# Power_Board_v2.net
KiCad netlist of a schematic drawn in EAGLE
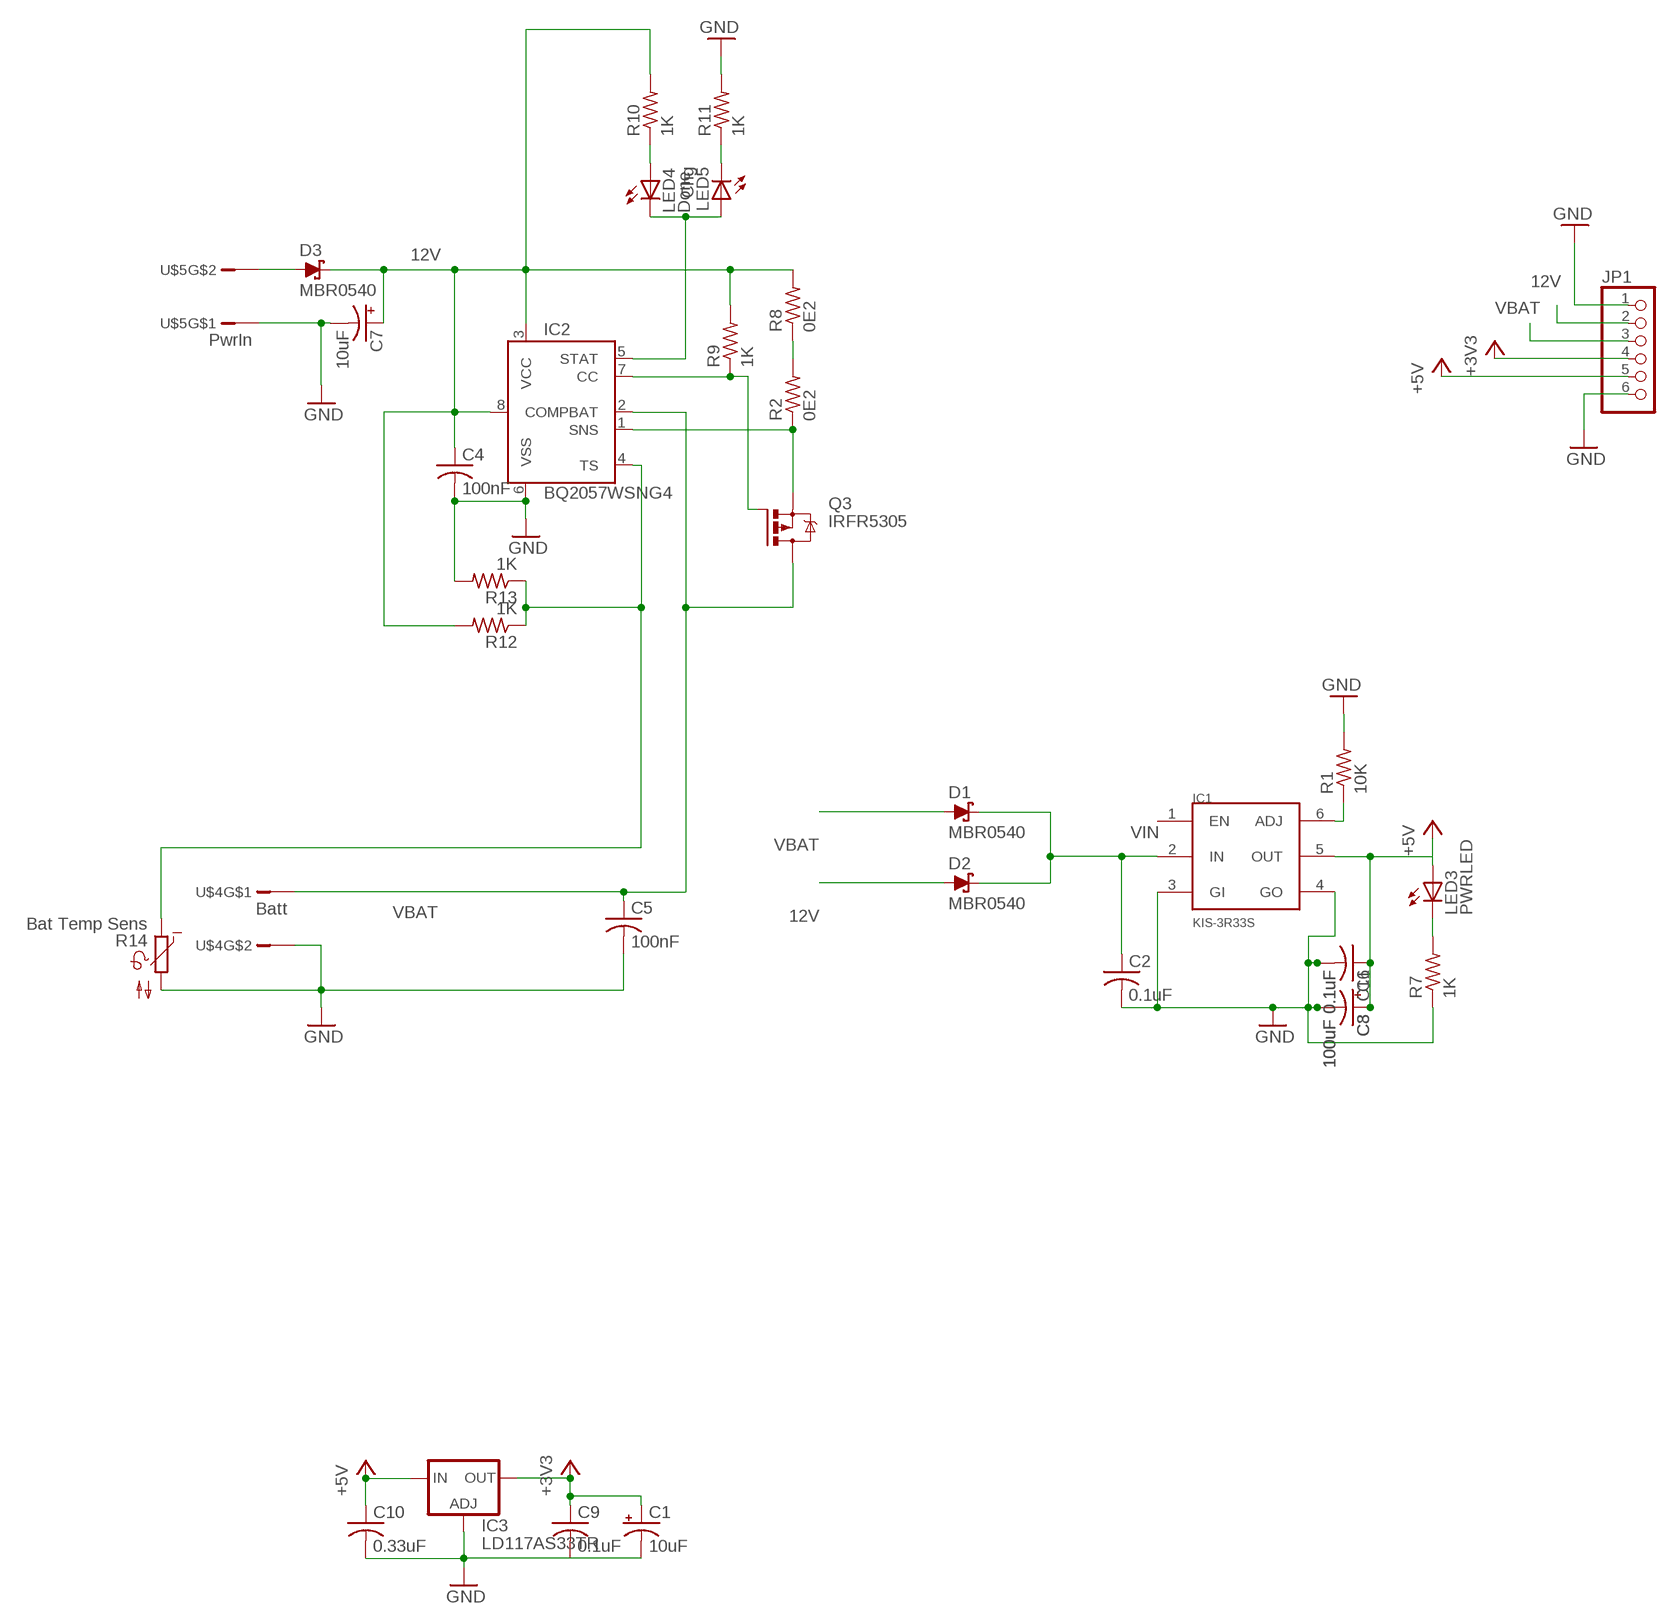
[diagram p0: schematic, sheet 1]

(export (version "E")
  (design (tool "Eeschema 10.0.6"))
  (components
    (comp (ref "C1")
      (value "10uF")
      (footprint "eagle-import:153CLV-0405")
      (libsource (lib "eagle-import") (part "CPOL-US153CLV-0405"))
    )
    (comp (ref "C2")
      (value "0.1uF")
      (footprint "eagle-import:C0805K")
      (libsource (lib "eagle-import") (part "C-USC0805K"))
    )
    (comp (ref "C3")
      (value "100uF")
      (footprint "eagle-import:PANASONIC_D")
      (libsource (lib "eagle-import") (part "CPOL-USD"))
    )
    (comp (ref "C4")
      (value "100nF")
      (footprint "eagle-import:C0805K")
      (libsource (lib "eagle-import") (part "C-USC0805K"))
    )
    (comp (ref "C5")
      (value "100nF")
      (footprint "eagle-import:C0805K")
      (libsource (lib "eagle-import") (part "C-USC0805K"))
    )
    (comp (ref "C6")
      (value "0.1uF")
      (footprint "eagle-import:C0805K")
      (libsource (lib "eagle-import") (part "C-USC0805K"))
    )
    (comp (ref "C7")
      (value "10uF")
      (footprint "eagle-import:153CLV-0405")
      (libsource (lib "eagle-import") (part "CPOL-US153CLV-0405"))
    )
    (comp (ref "C8")
      (value "100uF")
      (footprint "eagle-import:PANASONIC_D")
      (libsource (lib "eagle-import") (part "CPOL-USD"))
    )
    (comp (ref "C9")
      (value "0.1uF")
      (footprint "eagle-import:C0805K")
      (libsource (lib "eagle-import") (part "C-USC0805K"))
    )
    (comp (ref "C10")
      (value "0.33uF")
      (footprint "eagle-import:C0805K")
      (libsource (lib "eagle-import") (part "C-USC0805K"))
    )
    (comp (ref "C11")
      (value "0.1uF")
      (footprint "eagle-import:C0805K")
      (libsource (lib "eagle-import") (part "C-USC0805K"))
    )
    (comp (ref "D1")
      (value "MBR0540")
      (footprint "eagle-import:SOD123")
      (libsource (lib "eagle-import") (part "MBR0540"))
    )
    (comp (ref "D2")
      (value "MBR0540")
      (footprint "eagle-import:SOD123")
      (libsource (lib "eagle-import") (part "MBR0540"))
    )
    (comp (ref "D3")
      (value "MBR0540")
      (footprint "eagle-import:SOD123")
      (libsource (lib "eagle-import") (part "MBR0540"))
    )
    (comp (ref "IC1")
      (value "KIS-3R33S")
      (footprint "eagle-import:KIS-3R33S")
      (libsource (lib "eagle-import") (part "KIS-3R33S"))
    )
    (comp (ref "IC2")
      (value "BQ2057WSNG4")
      (footprint "eagle-import:D_R-PDSO-G8")
      (libsource (lib "eagle-import") (part "BQ2057WSNG4"))
    )
    (comp (ref "IC3")
      (value "LD117AS33TR")
      (footprint "eagle-import:SOT223")
      (libsource (lib "eagle-import") (part "LD117A?S33TR"))
    )
    (comp (ref "JP1")
      (value "PINHD-1X6")
      (footprint "eagle-import:1X06")
      (libsource (lib "eagle-import") (part "PINHD-1X6"))
    )
    (comp (ref "LED3")
      (value "PWRLED")
      (footprint "eagle-import:CHIPLED_0805")
      (libsource (lib "eagle-import") (part "LEDCHIPLED_0805"))
    )
    (comp (ref "LED4")
      (value "Done")
      (footprint "eagle-import:CHIPLED_0805")
      (libsource (lib "eagle-import") (part "LEDCHIPLED_0805"))
    )
    (comp (ref "LED5")
      (value "Chg")
      (footprint "eagle-import:CHIPLED_0805")
      (libsource (lib "eagle-import") (part "LEDCHIPLED_0805"))
    )
    (comp (ref "Q3")
      (value "IRFR5305")
      (footprint "eagle-import:D-PAK_TO252AA")
      (libsource (lib "eagle-import") (part "IRF?5305R"))
    )
    (comp (ref "R1")
      (value "10K")
      (footprint "eagle-import:R0805")
      (libsource (lib "eagle-import") (part "R-US_R0805"))
    )
    (comp (ref "R2")
      (value "0E2")
      (footprint "eagle-import:M1206")
      (libsource (lib "eagle-import") (part "R-US_M1206"))
    )
    (comp (ref "R7")
      (value "1K")
      (footprint "eagle-import:R0805")
      (libsource (lib "eagle-import") (part "R-US_R0805"))
    )
    (comp (ref "R8")
      (value "0E2")
      (footprint "eagle-import:M1206")
      (libsource (lib "eagle-import") (part "R-US_M1206"))
    )
    (comp (ref "R9")
      (value "1K")
      (footprint "eagle-import:R0805")
      (libsource (lib "eagle-import") (part "R-US_R0805"))
    )
    (comp (ref "R10")
      (value "1K")
      (footprint "eagle-import:R0805")
      (libsource (lib "eagle-import") (part "R-US_R0805"))
    )
    (comp (ref "R11")
      (value "1K")
      (footprint "eagle-import:R0805")
      (libsource (lib "eagle-import") (part "R-US_R0805"))
    )
    (comp (ref "R12")
      (value "1K")
      (footprint "eagle-import:R0805")
      (libsource (lib "eagle-import") (part "R-US_R0805"))
    )
    (comp (ref "R13")
      (value "1K")
      (footprint "eagle-import:R0805")
      (libsource (lib "eagle-import") (part "R-US_R0805"))
    )
    (comp (ref "R14")
      (value "Bat Temp Sens")
      (footprint "eagle-import:P640")
      (libsource (lib "eagle-import") (part "NTC640"))
    )
    (comp (ref "U$4")
      (value "Batt")
      (footprint "eagle-import:PHR-2")
      (libsource (lib "eagle-import") (part "JST_PHR-2"))
    )
    (comp (ref "U$5")
      (value "PwrIn")
      (footprint "eagle-import:PHR-2")
      (libsource (lib "eagle-import") (part "JST_PHR-2"))
    )
  )
  (nets
    (net (code "1") (name "+3V3") (class "Default")
      (node (ref "C1") (pin "+") (pinfunction "+_+") (pintype "passive"))
      (node (ref "C9") (pin "1") (pinfunction "1_1") (pintype "passive"))
      (node (ref "IC3") (pin "4") (pinfunction "OUT_4") (pintype "passive"))
      (node (ref "JP1") (pin "4") (pinfunction "4_4") (pintype "passive"))
    )
    (net (code "2") (name "+5V") (class "Default")
      (node (ref "C10") (pin "1") (pinfunction "1_1") (pintype "passive"))
      (node (ref "C11") (pin "1") (pinfunction "1_1") (pintype "passive"))
      (node (ref "C3") (pin "+") (pinfunction "+_+") (pintype "passive"))
      (node (ref "C6") (pin "1") (pinfunction "1_1") (pintype "passive"))
      (node (ref "C8") (pin "+") (pinfunction "+_+") (pintype "passive"))
      (node (ref "IC1") (pin "5") (pinfunction "OUT_5") (pintype "bidirectional"))
      (node (ref "IC3") (pin "3") (pinfunction "IN_3") (pintype "input"))
      (node (ref "JP1") (pin "5") (pinfunction "5_5") (pintype "passive"))
      (node (ref "LED3") (pin "A") (pinfunction "A_A") (pintype "passive"))
    )
    (net (code "3") (name "/12V") (class "Default")
      (node (ref "C4") (pin "1") (pinfunction "1_1") (pintype "passive"))
      (node (ref "C7") (pin "+") (pinfunction "+_+") (pintype "passive"))
      (node (ref "D2") (pin "A") (pinfunction "A_A") (pintype "passive"))
      (node (ref "D3") (pin "C") (pinfunction "C_C") (pintype "passive"))
      (node (ref "IC2") (pin "3") (pinfunction "VCC_3") (pintype "input"))
      (node (ref "IC2") (pin "8") (pinfunction "COMP_8") (pintype "input"))
      (node (ref "JP1") (pin "2") (pinfunction "2_2") (pintype "passive"))
      (node (ref "R10") (pin "2") (pinfunction "2_2") (pintype "passive"))
      (node (ref "R12") (pin "2") (pinfunction "2_2") (pintype "passive"))
      (node (ref "R8") (pin "2") (pinfunction "2_2") (pintype "passive"))
      (node (ref "R9") (pin "2") (pinfunction "2_2") (pintype "passive"))
    )
    (net (code "4") (name "/VBAT") (class "Default")
      (node (ref "C5") (pin "1") (pinfunction "1_1") (pintype "passive"))
      (node (ref "D1") (pin "A") (pinfunction "A_A") (pintype "passive"))
      (node (ref "IC2") (pin "2") (pinfunction "BAT_2") (pintype "input"))
      (node (ref "JP1") (pin "3") (pinfunction "3_3") (pintype "passive"))
      (node (ref "Q3") (pin "4") (pinfunction "D_4") (pintype "passive"))
      (node (ref "U$4") (pin "P$1") (pinfunction "1_P$1") (pintype "passive"))
    )
    (net (code "5") (name "/VIN") (class "Default")
      (node (ref "C2") (pin "1") (pinfunction "1_1") (pintype "passive"))
      (node (ref "D1") (pin "C") (pinfunction "C_C") (pintype "passive"))
      (node (ref "D2") (pin "C") (pinfunction "C_C") (pintype "passive"))
      (node (ref "IC1") (pin "2") (pinfunction "IN_2") (pintype "bidirectional"))
    )
    (net (code "6") (name "GND") (class "Default")
      (node (ref "C1") (pin "-") (pinfunction "-_-") (pintype "passive"))
      (node (ref "C10") (pin "2") (pinfunction "2_2") (pintype "passive"))
      (node (ref "C11") (pin "2") (pinfunction "2_2") (pintype "passive"))
      (node (ref "C2") (pin "2") (pinfunction "2_2") (pintype "passive"))
      (node (ref "C3") (pin "-") (pinfunction "-_-") (pintype "passive"))
      (node (ref "C4") (pin "2") (pinfunction "2_2") (pintype "passive"))
      (node (ref "C5") (pin "2") (pinfunction "2_2") (pintype "passive"))
      (node (ref "C6") (pin "2") (pinfunction "2_2") (pintype "passive"))
      (node (ref "C7") (pin "-") (pinfunction "-_-") (pintype "passive"))
      (node (ref "C8") (pin "-") (pinfunction "-_-") (pintype "passive"))
      (node (ref "C9") (pin "2") (pinfunction "2_2") (pintype "passive"))
      (node (ref "IC1") (pin "3") (pinfunction "GI_3") (pintype "power_in"))
      (node (ref "IC1") (pin "4") (pinfunction "GO_4") (pintype "power_in"))
      (node (ref "IC2") (pin "6") (pinfunction "VSS_6") (pintype "power_in"))
      (node (ref "IC3") (pin "1") (pinfunction "ADJ_1") (pintype "input"))
      (node (ref "JP1") (pin "1") (pinfunction "1_1") (pintype "passive"))
      (node (ref "JP1") (pin "6") (pinfunction "6_6") (pintype "passive"))
      (node (ref "R1") (pin "2") (pinfunction "2_2") (pintype "passive"))
      (node (ref "R11") (pin "2") (pinfunction "2_2") (pintype "passive"))
      (node (ref "R13") (pin "2") (pinfunction "2_2") (pintype "passive"))
      (node (ref "R14") (pin "2") (pinfunction "2_2") (pintype "passive"))
      (node (ref "R7") (pin "1") (pinfunction "1_1") (pintype "passive"))
      (node (ref "U$4") (pin "P$2") (pinfunction "1_P$2") (pintype "passive"))
      (node (ref "U$5") (pin "P$1") (pinfunction "1_P$1") (pintype "passive"))
    )
    (net (code "7") (name "Net-(IC1-ADJ)") (class "Default")
      (node (ref "IC1") (pin "6") (pinfunction "ADJ_6") (pintype "bidirectional"))
      (node (ref "R1") (pin "1") (pinfunction "1_1") (pintype "passive"))
    )
    (net (code "8") (name "Net-(IC2-CC)") (class "Default")
      (node (ref "IC2") (pin "7") (pinfunction "CC_7") (pintype "output"))
      (node (ref "Q3") (pin "1") (pinfunction "G_1") (pintype "passive"))
      (node (ref "R9") (pin "1") (pinfunction "1_1") (pintype "passive"))
    )
    (net (code "9") (name "Net-(IC2-SNS)") (class "Default")
      (node (ref "IC2") (pin "1") (pinfunction "SNS_1") (pintype "input"))
      (node (ref "Q3") (pin "3") (pinfunction "S_3") (pintype "passive"))
      (node (ref "R2") (pin "1") (pinfunction "1_1") (pintype "passive"))
    )
    (net (code "10") (name "Net-(IC2-STAT)") (class "Default")
      (node (ref "IC2") (pin "5") (pinfunction "STAT_5") (pintype "output"))
      (node (ref "LED4") (pin "C") (pinfunction "C_C") (pintype "passive"))
      (node (ref "LED5") (pin "A") (pinfunction "A_A") (pintype "passive"))
    )
    (net (code "11") (name "Net-(IC2-TS)") (class "Default")
      (node (ref "IC2") (pin "4") (pinfunction "TS_4") (pintype "input"))
      (node (ref "R12") (pin "1") (pinfunction "1_1") (pintype "passive"))
      (node (ref "R13") (pin "1") (pinfunction "1_1") (pintype "passive"))
      (node (ref "R14") (pin "1") (pinfunction "1_1") (pintype "passive"))
    )
    (net (code "12") (name "Net-(LED3-PadC)") (class "Default")
      (node (ref "LED3") (pin "C") (pinfunction "C_C") (pintype "passive"))
      (node (ref "R7") (pin "2") (pinfunction "2_2") (pintype "passive"))
    )
    (net (code "13") (name "Net-(LED4-PadA)") (class "Default")
      (node (ref "LED4") (pin "A") (pinfunction "A_A") (pintype "passive"))
      (node (ref "R10") (pin "1") (pinfunction "1_1") (pintype "passive"))
    )
    (net (code "14") (name "Net-(LED5-PadC)") (class "Default")
      (node (ref "LED5") (pin "C") (pinfunction "C_C") (pintype "passive"))
      (node (ref "R11") (pin "1") (pinfunction "1_1") (pintype "passive"))
    )
    (net (code "15") (name "Net-(R2-Pad2)") (class "Default")
      (node (ref "R2") (pin "2") (pinfunction "2_2") (pintype "passive"))
      (node (ref "R8") (pin "1") (pinfunction "1_1") (pintype "passive"))
    )
    (net (code "16") (name "Net-(U$5B-1)") (class "Default")
      (node (ref "D3") (pin "A") (pinfunction "A_A") (pintype "passive"))
      (node (ref "U$5") (pin "P$2") (pinfunction "1_P$2") (pintype "passive"))
    )
    (net (code "17") (name "unconnected-(IC1-EN-Pad1)") (class "Default")
      (node (ref "IC1") (pin "1") (pinfunction "EN_1") (pintype "bidirectional"))
    )
  )
)
